# SCH_the-first-of-many_2024-05-29.net
KiCad netlist of a schematic drawn in EasyEDA
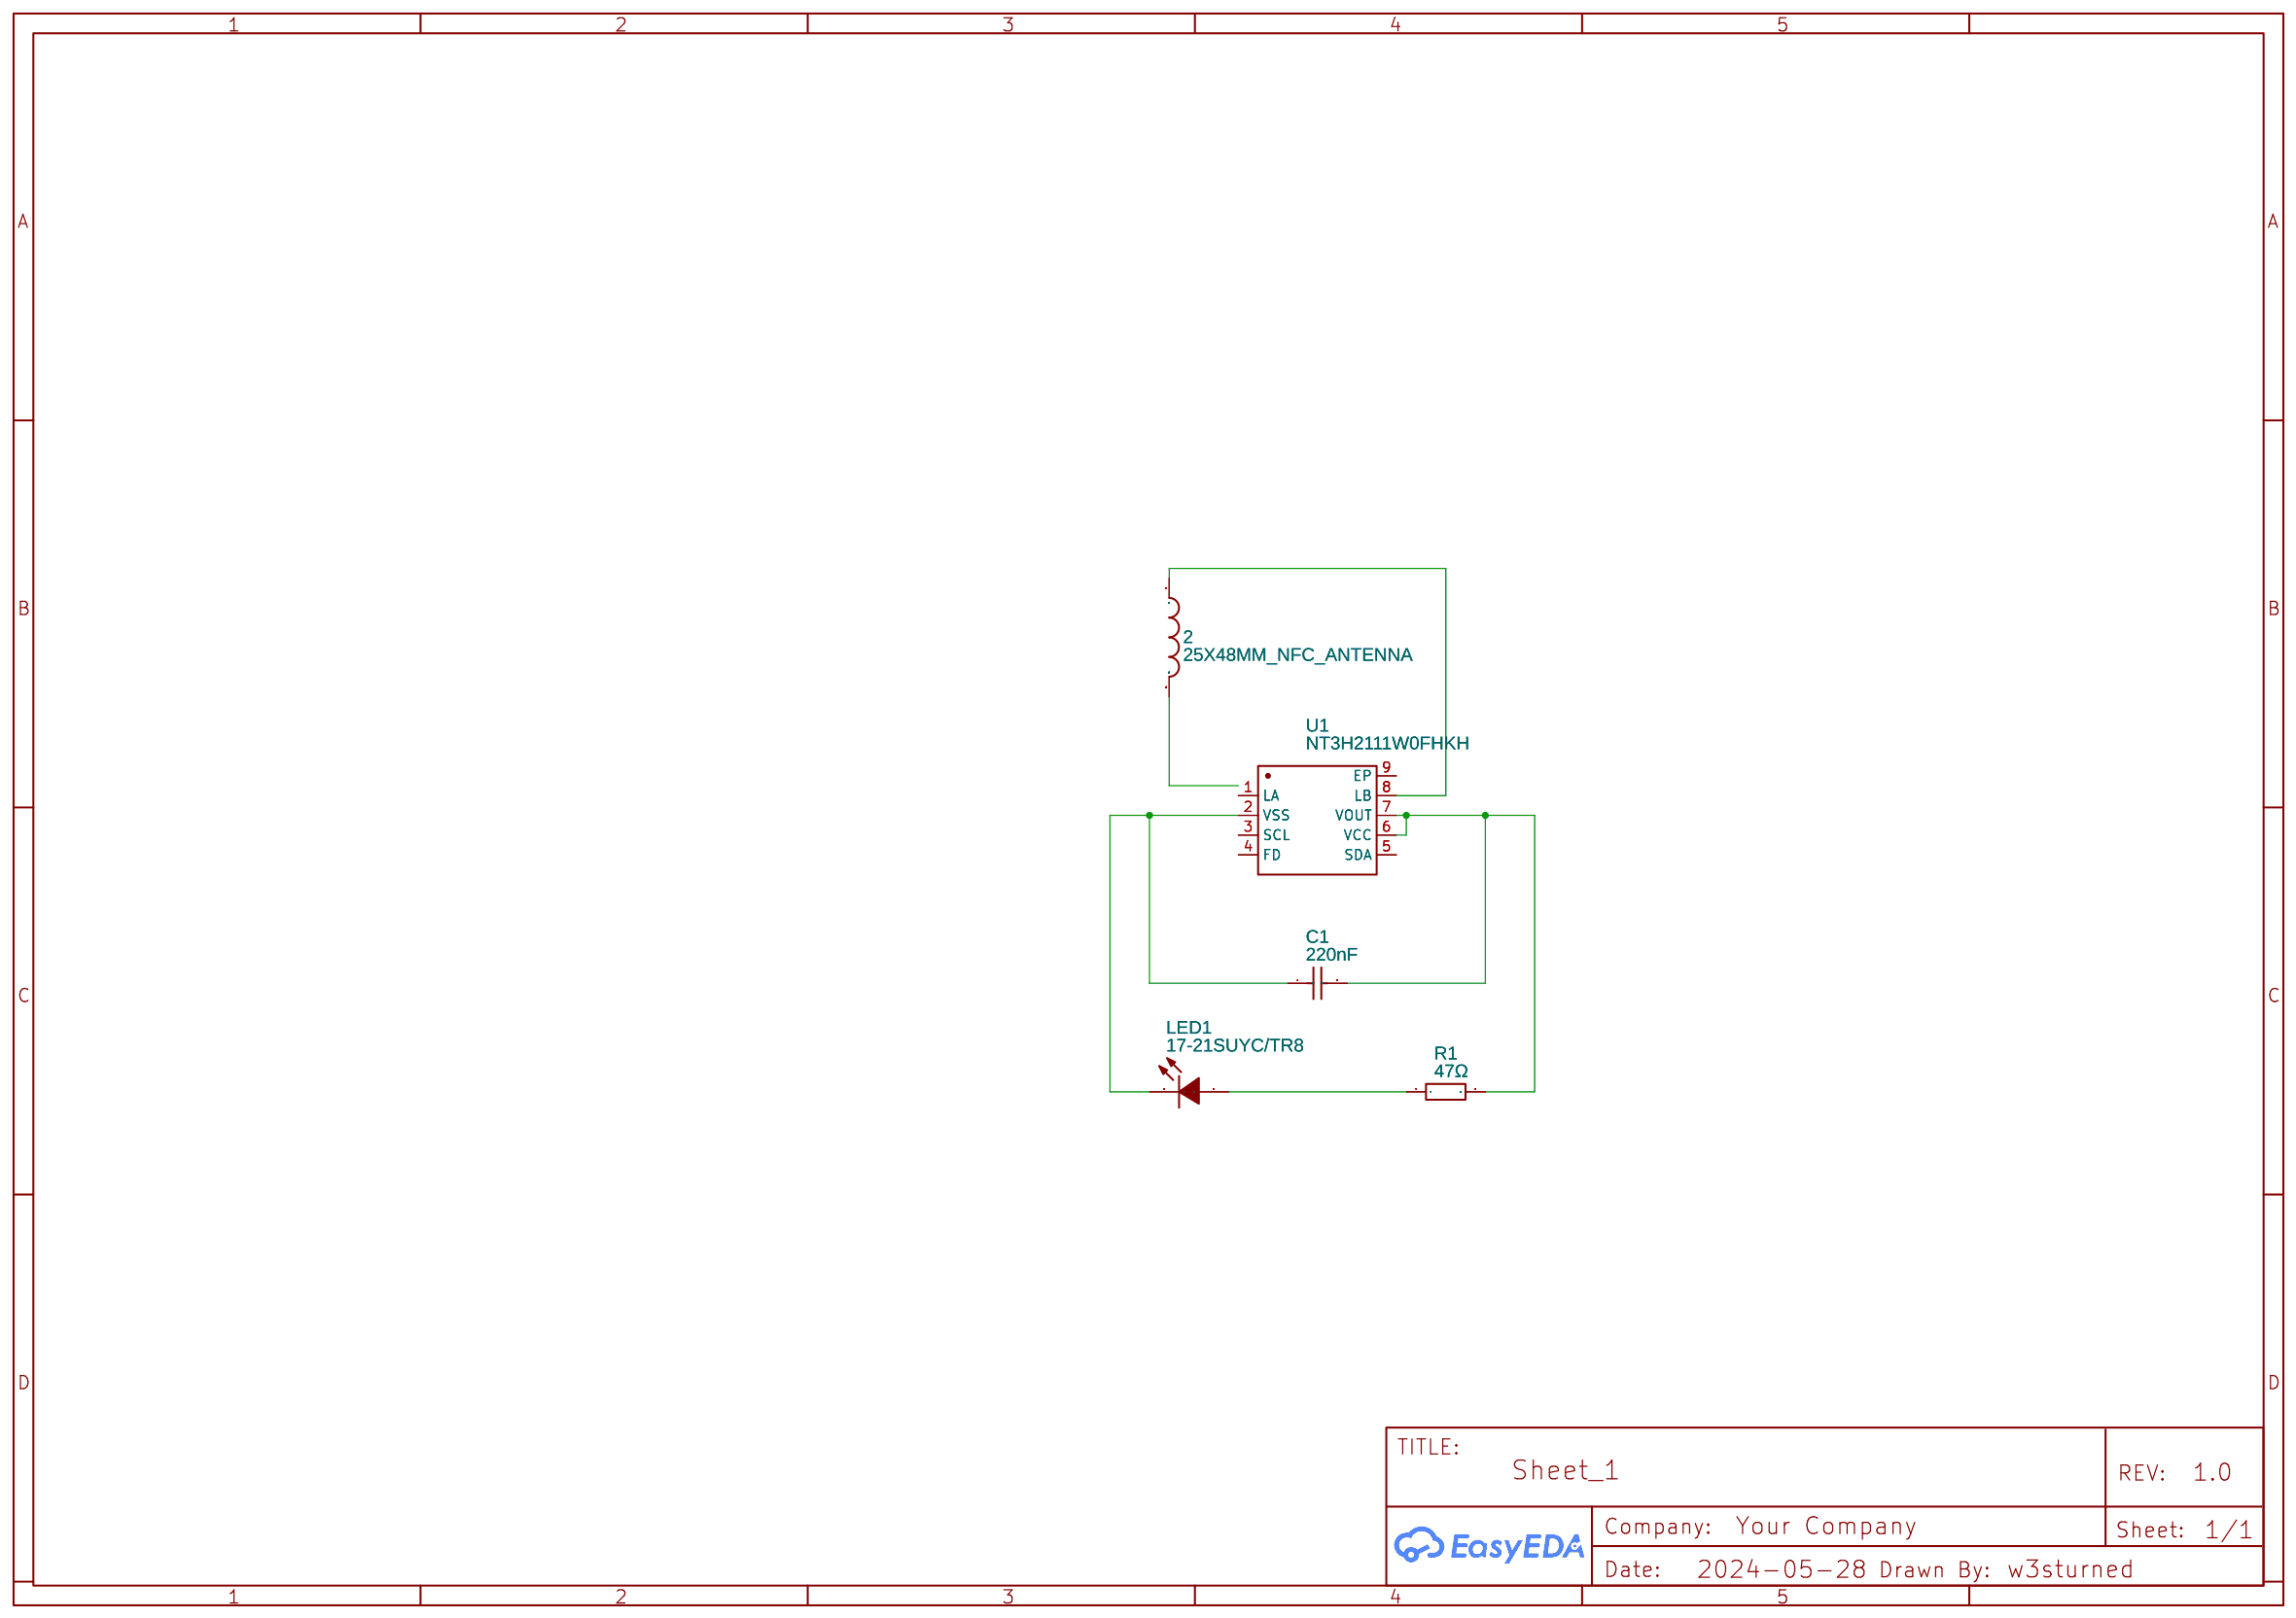
[diagram p0: schematic sheet]

(export (version "E")
  (design (tool "Eeschema 10.0.6"))
  (components
    (comp (ref "2") (value "25X48MM_NFC_ANTENNA") (libsource (lib "") (part "25X48MM_NFC_ANTENNA")))
    (comp (ref "C1")
      (value "220nF")
      (fields
        (field (name "Manufacturer Part") "CL10B224KA8NNNC")
        (field (name "Manufacturer") "SAMSUNG(三星)")
      )
      (libsource (lib "") (part "CL10B224KA8NNNC"))
    )
    (comp (ref "LED1")
      (value "17-21SUYC/TR8")
      (fields (field (name "Manufacturer Part") "KT-0805黄灯") (field (name "Manufacturer") "KENTO"))
      (libsource (lib "") (part "17-21SUYC/TR8"))
    )
    (comp (ref "R1")
      (value "47Ω")
      (fields
        (field (name "Manufacturer Part") "0603WAF470JT5E")
        (field (name "Manufacturer") "UNI-ROYAL(厚声)")
      )
      (libsource (lib "") (part "0603WAF470JT5E"))
    )
    (comp (ref "U1")
      (value "NT3H2111W0FHKH")
      (fields (field (name "Manufacturer") "NXP(恩智浦)"))
      (libsource (lib "") (part "NT3H2111W0FHKH"))
    )
  )
  (nets
    (net (code "1") (name "Net-(LED1-+)") (class "Default")
      (node (ref "LED1") (pin "1") (pinfunction "+_1") (pintype "unspecified"))
      (node (ref "R1") (pin "1") (pinfunction "1_1") (pintype "input"))
    )
    (net (code "2") (name "Net-(LED1--)") (class "Default")
      (node (ref "C1") (pin "1") (pinfunction "1_1") (pintype "input"))
      (node (ref "LED1") (pin "2") (pinfunction "-_2") (pintype "unspecified"))
      (node (ref "U1") (pin "2") (pinfunction "VSS_2") (pintype "unspecified"))
    )
    (net (code "3") (name "Net-(U1-LB)") (class "Default")
      (node (ref "2") (pin "P$1") (pinfunction "P$1_P$1") (pintype "bidirectional"))
      (node (ref "U1") (pin "8") (pinfunction "LB_8") (pintype "unspecified"))
    )
    (net (code "4") (name "Net-(U1-VCC)") (class "Default")
      (node (ref "C1") (pin "2") (pinfunction "2_2") (pintype "input"))
      (node (ref "R1") (pin "2") (pinfunction "2_2") (pintype "input"))
      (node (ref "U1") (pin "6") (pinfunction "VCC_6") (pintype "unspecified"))
      (node (ref "U1") (pin "7") (pinfunction "VOUT_7") (pintype "unspecified"))
    )
    (net (code "5") (name "unconnected-(2-PadP$2)") (class "Default")
      (node (ref "2") (pin "P$2") (pinfunction "P$2_P$2") (pintype "bidirectional"))
    )
    (net (code "6") (name "unconnected-(U1-EP-Pad9)") (class "Default")
      (node (ref "U1") (pin "9") (pinfunction "EP_9") (pintype "unspecified"))
    )
    (net (code "7") (name "unconnected-(U1-FD-Pad4)") (class "Default")
      (node (ref "U1") (pin "4") (pinfunction "FD_4") (pintype "unspecified"))
    )
    (net (code "8") (name "unconnected-(U1-LA-Pad1)") (class "Default")
      (node (ref "U1") (pin "1") (pinfunction "LA_1") (pintype "unspecified"))
    )
    (net (code "9") (name "unconnected-(U1-SCL-Pad3)") (class "Default")
      (node (ref "U1") (pin "3") (pinfunction "SCL_3") (pintype "unspecified"))
    )
    (net (code "10") (name "unconnected-(U1-SDA-Pad5)") (class "Default")
      (node (ref "U1") (pin "5") (pinfunction "SDA_5") (pintype "unspecified"))
    )
  )
)
